# 24Vto48V.net
KiCad netlist of a schematic drawn in Altium Designer
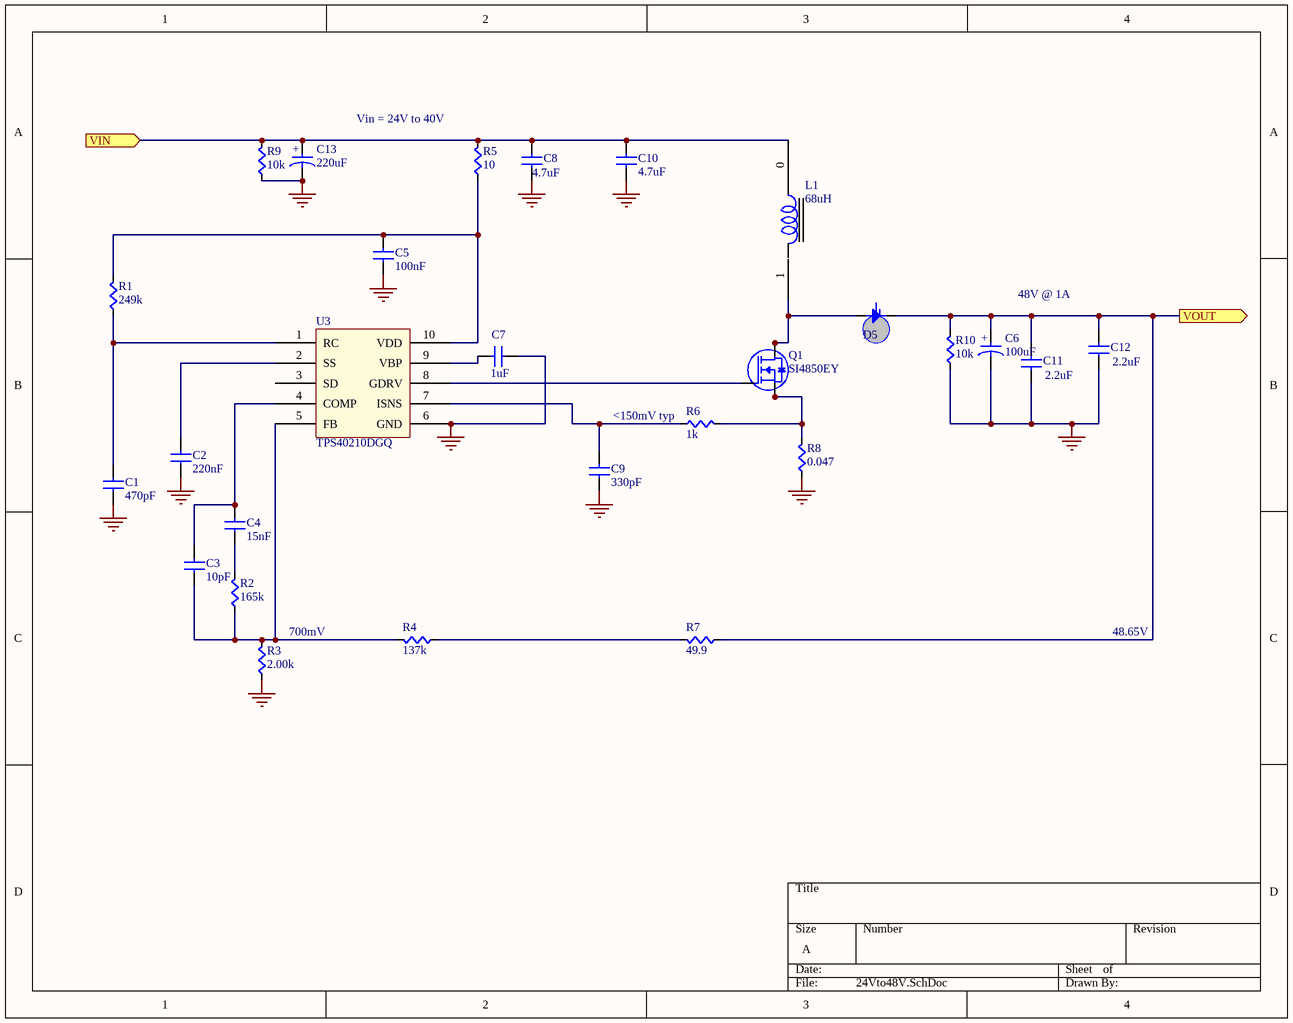
[diagram p0: 24Vto48V.SchDoc]

(export (version "E")
  (design (tool "Eeschema 10.0.6"))
  (components
    (comp (ref "C1")
      (value "470pF")
      (footprint "CAPC0603")
      (fields (field (name "Comment") "Cap"))
      (libsource (lib "Passives") (part "Cap"))
    )
    (comp (ref "C2")
      (value "220nF")
      (footprint "CAPC0603")
      (fields (field (name "Comment") "Cap"))
      (libsource (lib "Passives") (part "Cap"))
    )
    (comp (ref "C3")
      (value "10pF")
      (footprint "CAPC0603")
      (fields (field (name "Comment") "Cap"))
      (libsource (lib "Passives") (part "Cap"))
    )
    (comp (ref "C4")
      (value "15nF")
      (footprint "CAPC0603")
      (fields (field (name "Comment") "Cap"))
      (libsource (lib "Passives") (part "Cap"))
    )
    (comp (ref "C5")
      (value "100nF")
      (footprint "CAPC0603")
      (fields (field (name "Comment") "Cap"))
      (libsource (lib "Passives") (part "Cap"))
    )
    (comp (ref "C6")
      (value "100uF")
      (footprint "Passives:PCE3917CT-ND")
      (description "CAP ALUM 100UF 20% 50V SMD")
      (fields (field (name "Comment") "Cap Tant"))
      (libsource (lib "Passives") (part "CapPol"))
    )
    (comp (ref "C7")
      (value "1uF")
      (footprint "CAPC0603")
      (fields (field (name "Comment") "Cap"))
      (libsource (lib "Passives") (part "Cap"))
    )
    (comp (ref "C8")
      (value "4.7uF")
      (footprint "CAP1210")
      (description "CAP CER 10UF 50V 20% X5R 1210")
      (fields (field (name "Comment") "CAP1210"))
      (libsource (lib "Passives") (part "CAP1210"))
    )
    (comp (ref "C9")
      (value "330pF")
      (footprint "CAPC0603")
      (fields (field (name "Comment") "Cap"))
      (libsource (lib "Passives") (part "Cap"))
    )
    (comp (ref "C10")
      (value "4.7uF")
      (footprint "CAP1210")
      (description "CAP CER 10UF 50V 20% X5R 1210")
      (fields (field (name "Comment") "CAP1210"))
      (libsource (lib "Passives") (part "CAP1210"))
    )
    (comp (ref "C11")
      (value "2.2uF")
      (footprint "CAP1210")
      (description "CAP CER 10UF 50V 20% X5R 1210")
      (fields (field (name "Comment") "CAP1210"))
      (libsource (lib "Passives") (part "CAP1210"))
    )
    (comp (ref "C12")
      (value "2.2uF")
      (footprint "CAP1210")
      (description "CAP CER 10UF 50V 20% X5R 1210")
      (fields (field (name "Comment") "CAP1210"))
      (libsource (lib "Passives") (part "CAP1210"))
    )
    (comp (ref "C13")
      (value "220uF")
      (footprint "Passives:PCE3921CT-ND")
      (description "CAP ALUM 220UF 20% 50V SMD")
      (fields (field (name "Comment") "Cap Tant"))
      (libsource (lib "Passives") (part "CapPol"))
    )
    (comp (ref "D5")
      (value "Diode")
      (footprint "MBRS360SMB")
      (description "Standard Diode Template")
      (libsource (lib "Semiconductors") (part "Diode"))
    )
    (comp (ref "L1")
      (value "68uH")
      (footprint "732-1247-1-ND")
      (description "INDUCTOR 3.90UH 10.0A SMD")
      (fields (field (name "Comment") "37392C"))
      (libsource (lib "Passives") (part "37392C"))
    )
    (comp (ref "Q1")
      (value "SI4850EY")
      (footprint "SOIC-8-NO-EP")
      (description "MOSFET N-CH 60V 6A 8-SOIC")
      (libsource (lib "Semiconductors") (part "SI4850EY"))
    )
    (comp (ref "R1")
      (value "249k")
      (footprint "RES0603")
      (fields (field (name "Comment") "Res"))
      (libsource (lib "Passives") (part "Res"))
    )
    (comp (ref "R2")
      (value "165k")
      (footprint "RES0603")
      (fields (field (name "Comment") "Res"))
      (libsource (lib "Passives") (part "Res"))
    )
    (comp (ref "R3")
      (value "2.00k")
      (footprint "RES0603")
      (fields (field (name "Comment") "Res"))
      (libsource (lib "Passives") (part "Res"))
    )
    (comp (ref "R4")
      (value "137k")
      (footprint "RES0603")
      (fields (field (name "Comment") "Res"))
      (libsource (lib "Passives") (part "Res"))
    )
    (comp (ref "R5")
      (value "10")
      (footprint "RES0603")
      (fields (field (name "Comment") "Res"))
      (libsource (lib "Passives") (part "Res"))
    )
    (comp (ref "R6")
      (value "1k")
      (footprint "RES0603")
      (fields (field (name "Comment") "Res"))
      (libsource (lib "Passives") (part "Res"))
    )
    (comp (ref "R7")
      (value "49.9")
      (footprint "RES0603")
      (fields (field (name "Comment") "Res"))
      (libsource (lib "Passives") (part "Res"))
    )
    (comp (ref "R8")
      (value "0.047")
      (footprint "RES2512")
      (fields (field (name "Comment") "Res"))
      (libsource (lib "Passives") (part "Res"))
    )
    (comp (ref "R9")
      (value "10k")
      (footprint "RES0603")
      (fields (field (name "Comment") "Res"))
      (libsource (lib "Passives") (part "Res"))
    )
    (comp (ref "R10")
      (value "10k")
      (footprint "RES0603")
      (fields (field (name "Comment") "Res"))
      (libsource (lib "Passives") (part "Res"))
    )
    (comp (ref "U3")
      (value "TPS40210DGQ")
      (footprint "TPS40210")
      (libsource (lib "ICs") (part "TPS40210DGQ"))
    )
  )
  (nets
    (net (code "1") (name "/VIN") (class "Default")
      (node (ref "C10") (pin "1") (pinfunction "A_1") (pintype "passive"))
      (node (ref "C13") (pin "1") (pinfunction "A_1") (pintype "passive"))
      (node (ref "C8") (pin "1") (pinfunction "A_1") (pintype "passive"))
      (node (ref "L1") (pin "0") (pinfunction "0_0") (pintype "passive"))
      (node (ref "R5") (pin "1") (pinfunction "A_1") (pintype "passive"))
      (node (ref "R9") (pin "1") (pinfunction "A_1") (pintype "passive"))
    )
    (net (code "2") (name "/VOUT") (class "Default")
      (node (ref "C11") (pin "1") (pinfunction "A_1") (pintype "passive"))
      (node (ref "C12") (pin "1") (pinfunction "A_1") (pintype "passive"))
      (node (ref "C6") (pin "1") (pinfunction "A_1") (pintype "passive"))
      (node (ref "D5") (pin "C") (pinfunction "C_C") (pintype "passive"))
      (node (ref "R10") (pin "1") (pinfunction "A_1") (pintype "passive"))
      (node (ref "R7") (pin "2") (pinfunction "B_2") (pintype "passive"))
    )
    (net (code "3") (name "GND") (class "Default")
      (node (ref "C1") (pin "2") (pinfunction "B_2") (pintype "passive"))
      (node (ref "C10") (pin "2") (pinfunction "B_2") (pintype "passive"))
      (node (ref "C11") (pin "2") (pinfunction "B_2") (pintype "passive"))
      (node (ref "C12") (pin "2") (pinfunction "B_2") (pintype "passive"))
      (node (ref "C13") (pin "2") (pinfunction "B_2") (pintype "passive"))
      (node (ref "C2") (pin "2") (pinfunction "B_2") (pintype "passive"))
      (node (ref "C5") (pin "2") (pinfunction "B_2") (pintype "passive"))
      (node (ref "C6") (pin "2") (pinfunction "B_2") (pintype "passive"))
      (node (ref "C7") (pin "2") (pinfunction "B_2") (pintype "passive"))
      (node (ref "C8") (pin "2") (pinfunction "B_2") (pintype "passive"))
      (node (ref "C9") (pin "2") (pinfunction "B_2") (pintype "passive"))
      (node (ref "R10") (pin "2") (pinfunction "B_2") (pintype "passive"))
      (node (ref "R3") (pin "2") (pinfunction "B_2") (pintype "passive"))
      (node (ref "R8") (pin "2") (pinfunction "B_2") (pintype "passive"))
      (node (ref "R9") (pin "2") (pinfunction "B_2") (pintype "passive"))
      (node (ref "U3") (pin "6") (pinfunction "GND_6") (pintype "passive"))
    )
    (net (code "4") (name "Net-(C1-A)") (class "Default")
      (node (ref "C1") (pin "1") (pinfunction "A_1") (pintype "passive"))
      (node (ref "R1") (pin "2") (pinfunction "B_2") (pintype "passive"))
      (node (ref "U3") (pin "1") (pinfunction "RC_1") (pintype "passive"))
    )
    (net (code "5") (name "Net-(C2-A)") (class "Default")
      (node (ref "C2") (pin "1") (pinfunction "A_1") (pintype "passive"))
      (node (ref "U3") (pin "2") (pinfunction "SS_2") (pintype "passive"))
    )
    (net (code "6") (name "Net-(C3-A)") (class "Default")
      (node (ref "C3") (pin "1") (pinfunction "A_1") (pintype "passive"))
      (node (ref "C4") (pin "1") (pinfunction "A_1") (pintype "passive"))
      (node (ref "U3") (pin "4") (pinfunction "COMP_4") (pintype "passive"))
    )
    (net (code "7") (name "Net-(C3-B)") (class "Default")
      (node (ref "C3") (pin "2") (pinfunction "B_2") (pintype "passive"))
      (node (ref "R2") (pin "2") (pinfunction "B_2") (pintype "passive"))
      (node (ref "R3") (pin "1") (pinfunction "A_1") (pintype "passive"))
      (node (ref "R4") (pin "1") (pinfunction "A_1") (pintype "passive"))
      (node (ref "U3") (pin "5") (pinfunction "FB_5") (pintype "passive"))
    )
    (net (code "8") (name "Net-(C4-B)") (class "Default")
      (node (ref "C4") (pin "2") (pinfunction "B_2") (pintype "passive"))
      (node (ref "R2") (pin "1") (pinfunction "A_1") (pintype "passive"))
    )
    (net (code "9") (name "Net-(C5-A)") (class "Default")
      (node (ref "C5") (pin "1") (pinfunction "A_1") (pintype "passive"))
      (node (ref "R1") (pin "1") (pinfunction "A_1") (pintype "passive"))
      (node (ref "R5") (pin "2") (pinfunction "B_2") (pintype "passive"))
      (node (ref "U3") (pin "10") (pinfunction "VDD_10") (pintype "passive"))
    )
    (net (code "10") (name "Net-(C7-A)") (class "Default")
      (node (ref "C7") (pin "1") (pinfunction "A_1") (pintype "passive"))
      (node (ref "U3") (pin "9") (pinfunction "VBP_9") (pintype "passive"))
    )
    (net (code "11") (name "Net-(C9-A)") (class "Default")
      (node (ref "C9") (pin "1") (pinfunction "A_1") (pintype "passive"))
      (node (ref "R6") (pin "2") (pinfunction "B_2") (pintype "passive"))
      (node (ref "U3") (pin "7") (pinfunction "ISNS_7") (pintype "passive"))
    )
    (net (code "12") (name "Net-(D5-PadA)") (class "Default")
      (node (ref "D5") (pin "A") (pinfunction "A_A") (pintype "passive"))
      (node (ref "L1") (pin "1") (pinfunction "1_1") (pintype "passive"))
      (node (ref "Q1") (pin "5") (pinfunction "D_5") (pintype "passive"))
      (node (ref "Q1") (pin "6") (pinfunction "D_6") (pintype "passive"))
      (node (ref "Q1") (pin "7") (pinfunction "D_7") (pintype "passive"))
      (node (ref "Q1") (pin "8") (pinfunction "D_8") (pintype "passive"))
    )
    (net (code "13") (name "Net-(Q1-G)") (class "Default")
      (node (ref "Q1") (pin "4") (pinfunction "G_4") (pintype "passive"))
      (node (ref "U3") (pin "8") (pinfunction "GDRV_8") (pintype "passive"))
    )
    (net (code "14") (name "Net-(R4-B)") (class "Default")
      (node (ref "R4") (pin "2") (pinfunction "B_2") (pintype "passive"))
      (node (ref "R7") (pin "1") (pinfunction "A_1") (pintype "passive"))
    )
    (net (code "15") (name "Net-(R6-A)") (class "Default")
      (node (ref "Q1") (pin "1") (pinfunction "S_1") (pintype "passive"))
      (node (ref "Q1") (pin "2") (pinfunction "S_2") (pintype "passive"))
      (node (ref "Q1") (pin "3") (pinfunction "S_3") (pintype "passive"))
      (node (ref "R6") (pin "1") (pinfunction "A_1") (pintype "passive"))
      (node (ref "R8") (pin "1") (pinfunction "A_1") (pintype "passive"))
    )
    (net (code "16") (name "unconnected-(U3-SD-Pad3)") (class "Default")
      (node (ref "U3") (pin "3") (pinfunction "SD_3") (pintype "passive"))
    )
  )
)
